# flying-horse-foot.net
KiCad netlist of a schematic drawn in EAGLE
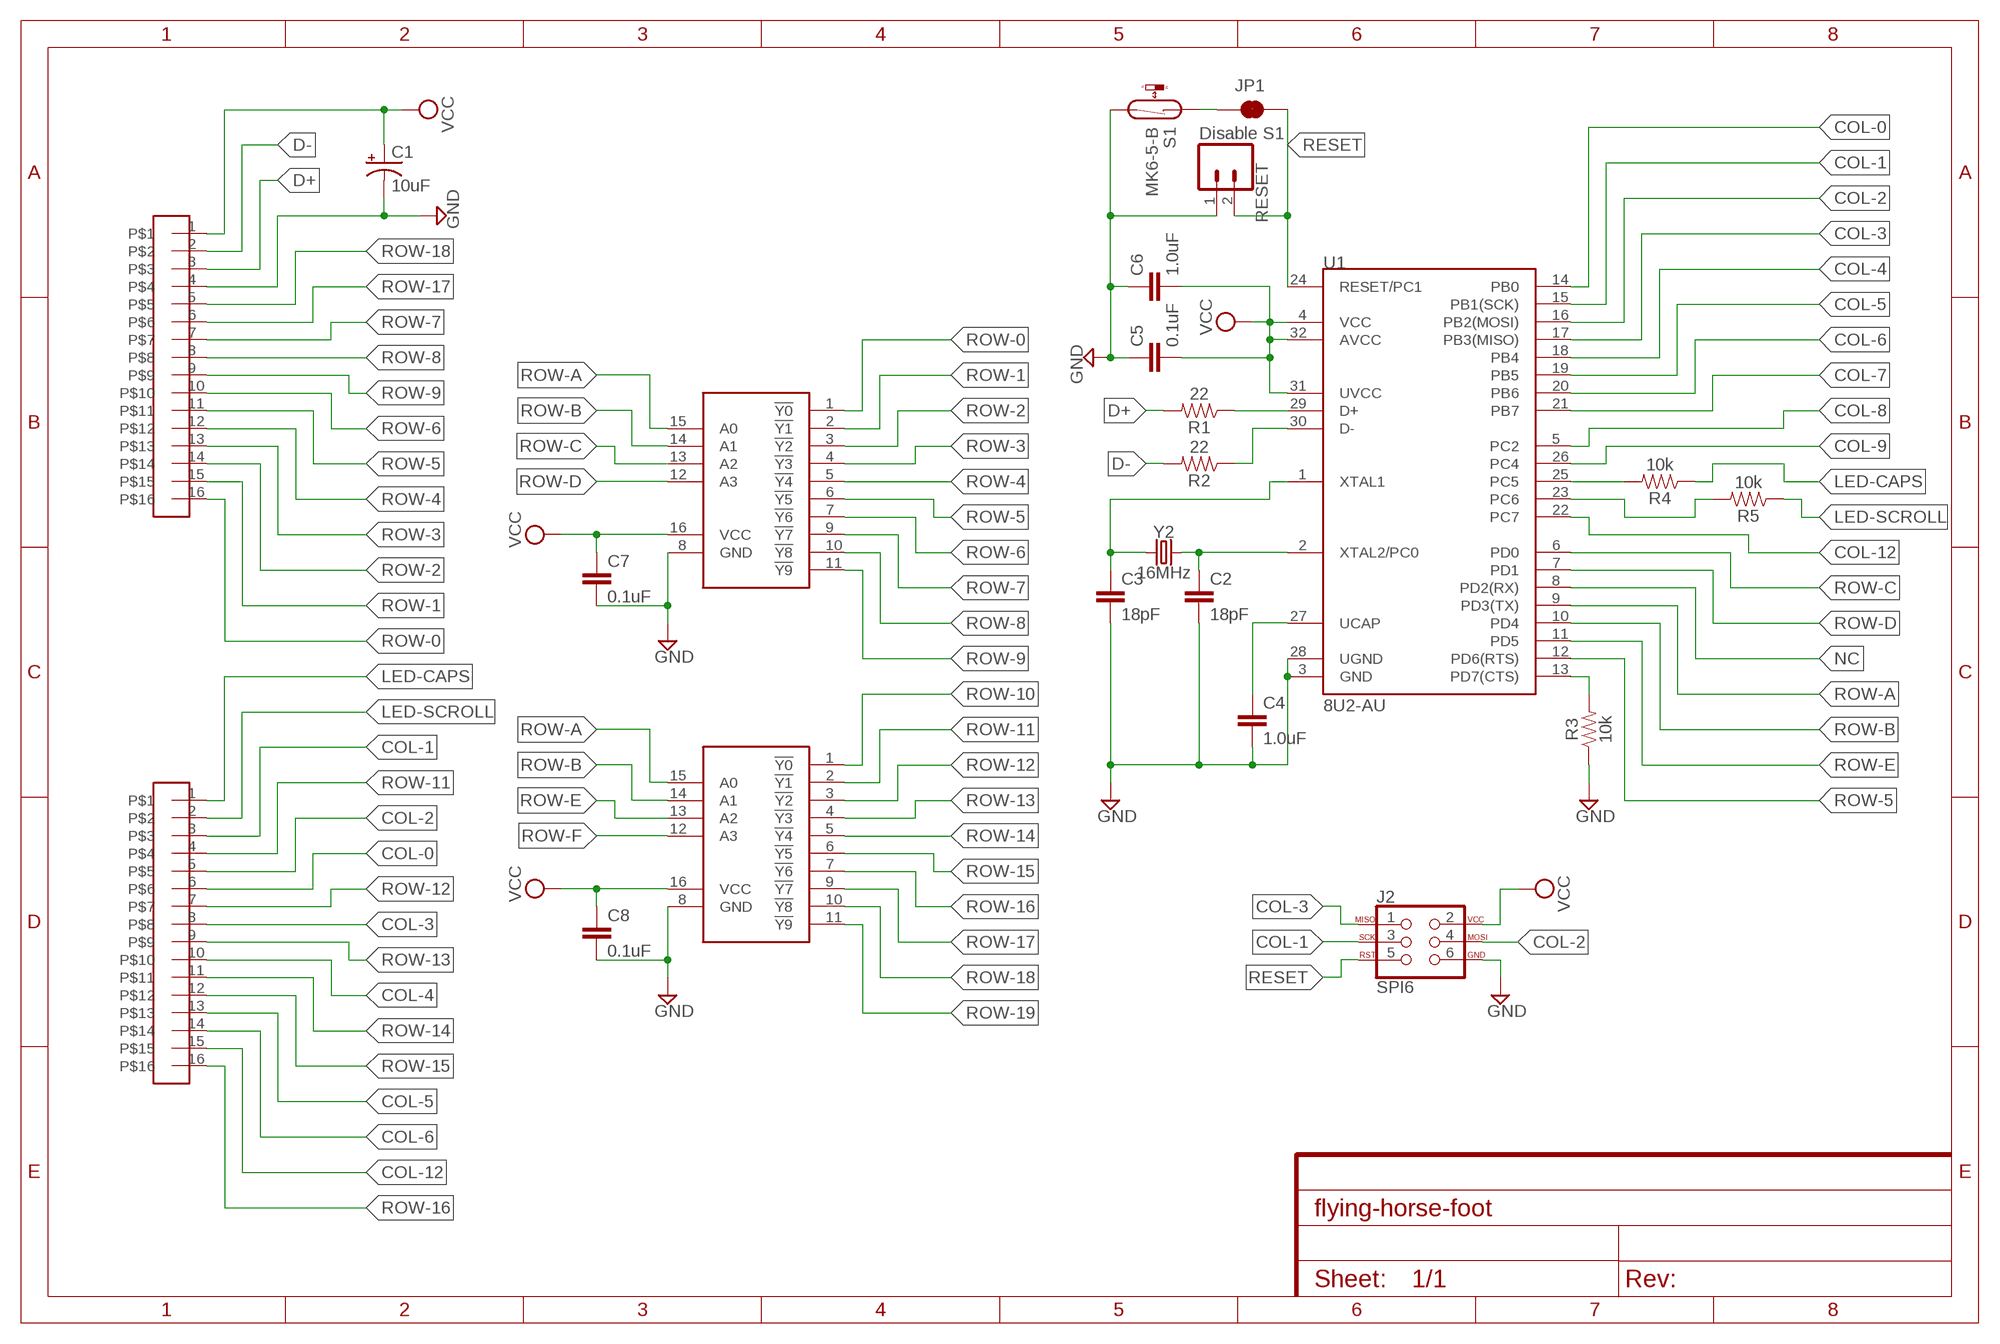
[diagram p0: schematic, sheet 1]

(export (version "E")
  (design (tool "Eeschema 10.0.6"))
  (components
    (comp (ref "C1")
      (value "10uF")
      (footprint "eagle-import:EEE-1CA100SR")
      (libsource (lib "eagle-import") (part "EEE-1CA100SR-EIA3528-20V-10%(TANT)"))
    )
    (comp (ref "C2")
      (value "18pF")
      (footprint "eagle-import:0603")
      (libsource (lib "eagle-import") (part "18PF-0603-50V-5%"))
    )
    (comp (ref "C3")
      (value "18pF")
      (footprint "eagle-import:0603")
      (libsource (lib "eagle-import") (part "18PF-0603-50V-5%"))
    )
    (comp (ref "C4")
      (value "1.0uF")
      (footprint "eagle-import:0603")
      (libsource (lib "eagle-import") (part "1.0UF-0603-16V-10%"))
    )
    (comp (ref "C5")
      (value "0.1uF")
      (footprint "eagle-import:0603")
      (libsource (lib "eagle-import") (part "0.1UF-0603-25V-5%"))
    )
    (comp (ref "C6")
      (value "1.0uF")
      (footprint "eagle-import:0603")
      (libsource (lib "eagle-import") (part "1.0UF-0603-16V-10%"))
    )
    (comp (ref "C7")
      (value "0.1uF")
      (footprint "eagle-import:0603")
      (libsource (lib "eagle-import") (part "0.1UF-0603-25V-5%"))
    )
    (comp (ref "C8")
      (value "0.1uF")
      (footprint "eagle-import:0603")
      (libsource (lib "eagle-import") (part "0.1UF-0603-25V-5%"))
    )
    (comp (ref "J2")
      (value "SPI6")
      (footprint "eagle-import:2X3-NS")
      (libsource (lib "eagle-import") (part "AVR_SPI_PROG_3X2NS"))
    )
    (comp (ref "JP1")
      (value "Disable S1")
      (footprint "eagle-import:SMT-JUMPER_2_NC_TRACE_NO-SILK")
      (libsource (lib "eagle-import") (part "JUMPER-SMT_2_NC_TRACE_NO-SILK"))
    )
    (comp (ref "R1")
      (value "22")
      (footprint "eagle-import:0603")
      (libsource (lib "eagle-import") (part "22OHM-0603-1/10W-1%"))
    )
    (comp (ref "R2")
      (value "22")
      (footprint "eagle-import:0603")
      (libsource (lib "eagle-import") (part "22OHM-0603-1/10W-1%"))
    )
    (comp (ref "R3")
      (value "10k")
      (footprint "eagle-import:0603")
      (libsource (lib "eagle-import") (part "10KOHM-0603-1/10W-1%"))
    )
    (comp (ref "R4")
      (value "10k")
      (footprint "eagle-import:0603")
      (libsource (lib "eagle-import") (part "10KOHM-0603-1/10W-1%"))
    )
    (comp (ref "R5")
      (value "10k")
      (footprint "eagle-import:0603")
      (libsource (lib "eagle-import") (part "10KOHM-0603-1/10W-1%"))
    )
    (comp (ref "RESET")
      (value "CONN_02")
      (footprint "eagle-import:1X02")
      (libsource (lib "eagle-import") (part "CONN_02"))
    )
    (comp (ref "S1")
      (value "MK6-5-B")
      (footprint "eagle-import:MK6-5")
      (fields (field (name "MF") "MEDER"))
      (libsource (lib "eagle-import") (part "REED-SWITCH-MK6-5-B"))
    )
    (comp (ref "U$1")
      (value "74HC42D16")
      (footprint "eagle-import:D16")
      (libsource (lib "eagle-import") (part "74HC42D16"))
    )
    (comp (ref "U$2")
      (value "74HC42D16")
      (footprint "eagle-import:D16")
      (libsource (lib "eagle-import") (part "74HC42D16"))
    )
    (comp (ref "U$3")
      (value "16PIN-2MM-HEADER")
      (footprint "eagle-import:16PIN-2MM-HEADER")
      (libsource (lib "eagle-import") (part "16PIN-2MM-HEADER"))
    )
    (comp (ref "U$4")
      (value "16PIN-2MM-HEADER")
      (footprint "eagle-import:16PIN-2MM-HEADER")
      (libsource (lib "eagle-import") (part "16PIN-2MM-HEADER"))
    )
    (comp (ref "U1")
      (value "8U2-AU")
      (footprint "eagle-import:TQFP32-08_MCU")
      (libsource (lib "eagle-import") (part "ATMEGA8U2AU"))
    )
    (comp (ref "Y2")
      (value "16MHz")
      (footprint "eagle-import:CRYSTAL-SMD-5X3.2-4PAD")
      (libsource (lib "eagle-import") (part "CRYSTAL-16MHZSMD-5X3.2"))
    )
  )
  (nets
    (net (code "1") (name "COL-0") (class "Default")
      (node (ref "U$4") (pin "6") (pinfunction "P$6_6") (pintype "bidirectional"))
      (node (ref "U1") (pin "14") (pinfunction "PB0_14") (pintype "bidirectional"))
    )
    (net (code "2") (name "COL-1") (class "Default")
      (node (ref "J2") (pin "3") (pinfunction "3_3") (pintype "passive"))
      (node (ref "U$4") (pin "3") (pinfunction "P$3_3") (pintype "bidirectional"))
      (node (ref "U1") (pin "15") (pinfunction "PB1(SCK)_15") (pintype "bidirectional"))
    )
    (net (code "3") (name "COL-2") (class "Default")
      (node (ref "J2") (pin "4") (pinfunction "4_4") (pintype "passive"))
      (node (ref "U$4") (pin "5") (pinfunction "P$5_5") (pintype "bidirectional"))
      (node (ref "U1") (pin "16") (pinfunction "PB2(MOSI)_16") (pintype "bidirectional"))
    )
    (net (code "4") (name "COL-3") (class "Default")
      (node (ref "J2") (pin "1") (pinfunction "1_1") (pintype "passive"))
      (node (ref "U$4") (pin "8") (pinfunction "P$8_8") (pintype "bidirectional"))
      (node (ref "U1") (pin "17") (pinfunction "PB3(MISO)_17") (pintype "bidirectional"))
    )
    (net (code "5") (name "COL-4") (class "Default")
      (node (ref "U$4") (pin "10") (pinfunction "P$10_10") (pintype "bidirectional"))
      (node (ref "U1") (pin "18") (pinfunction "PB4_18") (pintype "bidirectional"))
    )
    (net (code "6") (name "COL-5") (class "Default")
      (node (ref "U$4") (pin "13") (pinfunction "P$13_13") (pintype "bidirectional"))
      (node (ref "U1") (pin "19") (pinfunction "PB5_19") (pintype "bidirectional"))
    )
    (net (code "7") (name "COL-6") (class "Default")
      (node (ref "U$4") (pin "14") (pinfunction "P$14_14") (pintype "bidirectional"))
      (node (ref "U1") (pin "20") (pinfunction "PB6_20") (pintype "bidirectional"))
    )
    (net (code "8") (name "COL-7") (class "Default")
      (node (ref "U1") (pin "21") (pinfunction "PB7_21") (pintype "bidirectional"))
    )
    (net (code "9") (name "COL-8") (class "Default")
      (node (ref "U1") (pin "5") (pinfunction "PC2_5") (pintype "bidirectional"))
    )
    (net (code "10") (name "COL-9") (class "Default")
      (node (ref "U1") (pin "26") (pinfunction "PC4_26") (pintype "bidirectional"))
    )
    (net (code "11") (name "COL-12") (class "Default")
      (node (ref "U$4") (pin "15") (pinfunction "P$15_15") (pintype "bidirectional"))
      (node (ref "U1") (pin "22") (pinfunction "PC7_22") (pintype "bidirectional"))
    )
    (net (code "12") (name "D+") (class "Default")
      (node (ref "R1") (pin "2") (pinfunction "2_2") (pintype "passive"))
      (node (ref "U$3") (pin "3") (pinfunction "P$3_3") (pintype "bidirectional"))
    )
    (net (code "13") (name "D-") (class "Default")
      (node (ref "R2") (pin "2") (pinfunction "2_2") (pintype "passive"))
      (node (ref "U$3") (pin "2") (pinfunction "P$2_2") (pintype "bidirectional"))
    )
    (net (code "14") (name "GND") (class "Default")
      (node (ref "C1") (pin "-") (pinfunction "-_-") (pintype "passive"))
      (node (ref "C2") (pin "2") (pinfunction "2_2") (pintype "passive"))
      (node (ref "C3") (pin "2") (pinfunction "2_2") (pintype "passive"))
      (node (ref "C4") (pin "2") (pinfunction "2_2") (pintype "passive"))
      (node (ref "C5") (pin "1") (pinfunction "1_1") (pintype "passive"))
      (node (ref "C6") (pin "1") (pinfunction "1_1") (pintype "passive"))
      (node (ref "C7") (pin "2") (pinfunction "2_2") (pintype "passive"))
      (node (ref "C8") (pin "2") (pinfunction "2_2") (pintype "passive"))
      (node (ref "J2") (pin "6") (pinfunction "6_6") (pintype "passive"))
      (node (ref "R3") (pin "1") (pinfunction "1_1") (pintype "passive"))
      (node (ref "RESET") (pin "1") (pinfunction "1_1") (pintype "passive"))
      (node (ref "S1") (pin "2") (pinfunction "2_2") (pintype "passive"))
      (node (ref "U$1") (pin "8") (pinfunction "GND_8") (pintype "bidirectional"))
      (node (ref "U$2") (pin "8") (pinfunction "GND_8") (pintype "bidirectional"))
      (node (ref "U$3") (pin "4") (pinfunction "P$4_4") (pintype "bidirectional"))
      (node (ref "U1") (pin "28") (pinfunction "UGND_28") (pintype "bidirectional"))
      (node (ref "U1") (pin "3") (pinfunction "GND_3") (pintype "bidirectional"))
    )
    (net (code "15") (name "LED-CAPS") (class "Default")
      (node (ref "R4") (pin "1") (pinfunction "1_1") (pintype "passive"))
      (node (ref "U$4") (pin "1") (pinfunction "P$1_1") (pintype "bidirectional"))
    )
    (net (code "16") (name "LED-SCROLL") (class "Default")
      (node (ref "R5") (pin "1") (pinfunction "1_1") (pintype "passive"))
      (node (ref "U$4") (pin "2") (pinfunction "P$2_2") (pintype "bidirectional"))
    )
    (net (code "17") (name "NC") (class "Default")
      (node (ref "U1") (pin "8") (pinfunction "PD2(RX)_8") (pintype "bidirectional"))
    )
    (net (code "18") (name "Net-(JP1-Pad1)") (class "Default")
      (node (ref "JP1") (pin "1") (pinfunction "1_1") (pintype "passive"))
      (node (ref "S1") (pin "1") (pinfunction "1_1") (pintype "passive"))
    )
    (net (code "19") (name "Net-(U1-D+)") (class "Default")
      (node (ref "R1") (pin "1") (pinfunction "1_1") (pintype "passive"))
      (node (ref "U1") (pin "29") (pinfunction "D+_29") (pintype "bidirectional"))
    )
    (net (code "20") (name "Net-(U1-D-)") (class "Default")
      (node (ref "R2") (pin "1") (pinfunction "1_1") (pintype "passive"))
      (node (ref "U1") (pin "30") (pinfunction "D-_30") (pintype "bidirectional"))
    )
    (net (code "21") (name "Net-(U1-PC5)") (class "Default")
      (node (ref "R4") (pin "2") (pinfunction "2_2") (pintype "passive"))
      (node (ref "U1") (pin "25") (pinfunction "PC5_25") (pintype "bidirectional"))
    )
    (net (code "22") (name "Net-(U1-PC6)") (class "Default")
      (node (ref "R5") (pin "2") (pinfunction "2_2") (pintype "passive"))
      (node (ref "U1") (pin "23") (pinfunction "PC6_23") (pintype "bidirectional"))
    )
    (net (code "23") (name "Net-(U1-PD7(CTS))") (class "Default")
      (node (ref "R3") (pin "2") (pinfunction "2_2") (pintype "passive"))
      (node (ref "U1") (pin "13") (pinfunction "PD7(CTS)_13") (pintype "bidirectional"))
    )
    (net (code "24") (name "Net-(U1-UCAP)") (class "Default")
      (node (ref "C4") (pin "1") (pinfunction "1_1") (pintype "passive"))
      (node (ref "U1") (pin "27") (pinfunction "UCAP_27") (pintype "bidirectional"))
    )
    (net (code "25") (name "Net-(U1-XTAL1)") (class "Default")
      (node (ref "C3") (pin "1") (pinfunction "1_1") (pintype "passive"))
      (node (ref "U1") (pin "1") (pinfunction "XTAL1_1") (pintype "bidirectional"))
      (node (ref "Y2") (pin "1") (pinfunction "1_1") (pintype "passive"))
    )
    (net (code "26") (name "Net-(U1-XTAL2{slash}PC0)") (class "Default")
      (node (ref "C2") (pin "1") (pinfunction "1_1") (pintype "passive"))
      (node (ref "U1") (pin "2") (pinfunction "XTAL2/PC0_2") (pintype "bidirectional"))
      (node (ref "Y2") (pin "3") (pinfunction "2_3") (pintype "passive"))
    )
    (net (code "27") (name "RESET") (class "Default")
      (node (ref "J2") (pin "5") (pinfunction "5_5") (pintype "passive"))
      (node (ref "JP1") (pin "2") (pinfunction "2_2") (pintype "passive"))
      (node (ref "RESET") (pin "2") (pinfunction "2_2") (pintype "passive"))
      (node (ref "U1") (pin "24") (pinfunction "RESET/PC1_24") (pintype "bidirectional"))
    )
    (net (code "28") (name "ROW-0") (class "Default")
      (node (ref "U$1") (pin "1") (pinfunction "~{Y0}_1") (pintype "bidirectional"))
      (node (ref "U$3") (pin "16") (pinfunction "P$16_16") (pintype "bidirectional"))
    )
    (net (code "29") (name "ROW-1") (class "Default")
      (node (ref "U$1") (pin "2") (pinfunction "~{Y1}_2") (pintype "bidirectional"))
      (node (ref "U$3") (pin "15") (pinfunction "P$15_15") (pintype "bidirectional"))
    )
    (net (code "30") (name "ROW-2") (class "Default")
      (node (ref "U$1") (pin "3") (pinfunction "~{Y2}_3") (pintype "bidirectional"))
      (node (ref "U$3") (pin "14") (pinfunction "P$14_14") (pintype "bidirectional"))
    )
    (net (code "31") (name "ROW-3") (class "Default")
      (node (ref "U$1") (pin "4") (pinfunction "~{Y3}_4") (pintype "bidirectional"))
      (node (ref "U$3") (pin "13") (pinfunction "P$13_13") (pintype "bidirectional"))
    )
    (net (code "32") (name "ROW-4") (class "Default")
      (node (ref "U$1") (pin "5") (pinfunction "~{Y4}_5") (pintype "bidirectional"))
      (node (ref "U$3") (pin "12") (pinfunction "P$12_12") (pintype "bidirectional"))
    )
    (net (code "33") (name "ROW-5") (class "Default")
      (node (ref "U$1") (pin "6") (pinfunction "~{Y5}_6") (pintype "bidirectional"))
      (node (ref "U$3") (pin "11") (pinfunction "P$11_11") (pintype "bidirectional"))
      (node (ref "U1") (pin "12") (pinfunction "PD6(RTS)_12") (pintype "bidirectional"))
    )
    (net (code "34") (name "ROW-6") (class "Default")
      (node (ref "U$1") (pin "7") (pinfunction "~{Y6}_7") (pintype "bidirectional"))
      (node (ref "U$3") (pin "10") (pinfunction "P$10_10") (pintype "bidirectional"))
    )
    (net (code "35") (name "ROW-7") (class "Default")
      (node (ref "U$1") (pin "9") (pinfunction "~{Y7}_9") (pintype "bidirectional"))
      (node (ref "U$3") (pin "7") (pinfunction "P$7_7") (pintype "bidirectional"))
    )
    (net (code "36") (name "ROW-8") (class "Default")
      (node (ref "U$1") (pin "10") (pinfunction "~{Y8}_10") (pintype "bidirectional"))
      (node (ref "U$3") (pin "8") (pinfunction "P$8_8") (pintype "bidirectional"))
    )
    (net (code "37") (name "ROW-9") (class "Default")
      (node (ref "U$1") (pin "11") (pinfunction "~{Y9}_11") (pintype "bidirectional"))
      (node (ref "U$3") (pin "9") (pinfunction "P$9_9") (pintype "bidirectional"))
    )
    (net (code "38") (name "ROW-10") (class "Default")
      (node (ref "U$2") (pin "1") (pinfunction "~{Y0}_1") (pintype "bidirectional"))
    )
    (net (code "39") (name "ROW-11") (class "Default")
      (node (ref "U$2") (pin "2") (pinfunction "~{Y1}_2") (pintype "bidirectional"))
      (node (ref "U$4") (pin "4") (pinfunction "P$4_4") (pintype "bidirectional"))
    )
    (net (code "40") (name "ROW-12") (class "Default")
      (node (ref "U$2") (pin "3") (pinfunction "~{Y2}_3") (pintype "bidirectional"))
      (node (ref "U$4") (pin "7") (pinfunction "P$7_7") (pintype "bidirectional"))
    )
    (net (code "41") (name "ROW-13") (class "Default")
      (node (ref "U$2") (pin "4") (pinfunction "~{Y3}_4") (pintype "bidirectional"))
      (node (ref "U$4") (pin "9") (pinfunction "P$9_9") (pintype "bidirectional"))
    )
    (net (code "42") (name "ROW-14") (class "Default")
      (node (ref "U$2") (pin "5") (pinfunction "~{Y4}_5") (pintype "bidirectional"))
      (node (ref "U$4") (pin "11") (pinfunction "P$11_11") (pintype "bidirectional"))
    )
    (net (code "43") (name "ROW-15") (class "Default")
      (node (ref "U$2") (pin "6") (pinfunction "~{Y5}_6") (pintype "bidirectional"))
      (node (ref "U$4") (pin "12") (pinfunction "P$12_12") (pintype "bidirectional"))
    )
    (net (code "44") (name "ROW-16") (class "Default")
      (node (ref "U$2") (pin "7") (pinfunction "~{Y6}_7") (pintype "bidirectional"))
      (node (ref "U$4") (pin "16") (pinfunction "P$16_16") (pintype "bidirectional"))
    )
    (net (code "45") (name "ROW-17") (class "Default")
      (node (ref "U$2") (pin "9") (pinfunction "~{Y7}_9") (pintype "bidirectional"))
      (node (ref "U$3") (pin "6") (pinfunction "P$6_6") (pintype "bidirectional"))
    )
    (net (code "46") (name "ROW-18") (class "Default")
      (node (ref "U$2") (pin "10") (pinfunction "~{Y8}_10") (pintype "bidirectional"))
      (node (ref "U$3") (pin "5") (pinfunction "P$5_5") (pintype "bidirectional"))
    )
    (net (code "47") (name "ROW-19") (class "Default")
      (node (ref "U$2") (pin "11") (pinfunction "~{Y9}_11") (pintype "bidirectional"))
    )
    (net (code "48") (name "ROW-A") (class "Default")
      (node (ref "U$1") (pin "15") (pinfunction "A0_15") (pintype "bidirectional"))
      (node (ref "U$2") (pin "15") (pinfunction "A0_15") (pintype "bidirectional"))
      (node (ref "U1") (pin "9") (pinfunction "PD3(TX)_9") (pintype "bidirectional"))
    )
    (net (code "49") (name "ROW-B") (class "Default")
      (node (ref "U$1") (pin "14") (pinfunction "A1_14") (pintype "bidirectional"))
      (node (ref "U$2") (pin "14") (pinfunction "A1_14") (pintype "bidirectional"))
      (node (ref "U1") (pin "10") (pinfunction "PD4_10") (pintype "bidirectional"))
    )
    (net (code "50") (name "ROW-C") (class "Default")
      (node (ref "U$1") (pin "13") (pinfunction "A2_13") (pintype "bidirectional"))
      (node (ref "U1") (pin "6") (pinfunction "PD0_6") (pintype "bidirectional"))
    )
    (net (code "51") (name "ROW-D") (class "Default")
      (node (ref "U$1") (pin "12") (pinfunction "A3_12") (pintype "bidirectional"))
      (node (ref "U1") (pin "7") (pinfunction "PD1_7") (pintype "bidirectional"))
    )
    (net (code "52") (name "ROW-E") (class "Default")
      (node (ref "U$2") (pin "13") (pinfunction "A2_13") (pintype "bidirectional"))
      (node (ref "U1") (pin "11") (pinfunction "PD5_11") (pintype "bidirectional"))
    )
    (net (code "53") (name "ROW-F") (class "Default")
      (node (ref "U$2") (pin "12") (pinfunction "A3_12") (pintype "bidirectional"))
    )
    (net (code "54") (name "VCC") (class "Default")
      (node (ref "C1") (pin "+") (pinfunction "+_+") (pintype "passive"))
      (node (ref "C5") (pin "2") (pinfunction "2_2") (pintype "passive"))
      (node (ref "C6") (pin "2") (pinfunction "2_2") (pintype "passive"))
      (node (ref "C7") (pin "1") (pinfunction "1_1") (pintype "passive"))
      (node (ref "C8") (pin "1") (pinfunction "1_1") (pintype "passive"))
      (node (ref "J2") (pin "2") (pinfunction "2_2") (pintype "passive"))
      (node (ref "U$1") (pin "16") (pinfunction "VCC_16") (pintype "bidirectional"))
      (node (ref "U$2") (pin "16") (pinfunction "VCC_16") (pintype "bidirectional"))
      (node (ref "U$3") (pin "1") (pinfunction "P$1_1") (pintype "bidirectional"))
      (node (ref "U1") (pin "31") (pinfunction "UVCC_31") (pintype "bidirectional"))
      (node (ref "U1") (pin "32") (pinfunction "AVCC_32") (pintype "bidirectional"))
      (node (ref "U1") (pin "4") (pinfunction "VCC_4") (pintype "bidirectional"))
    )
  )
)
